# Alim_Ticketing_Slave.net
KiCad netlist of a schematic drawn in Altium Designer
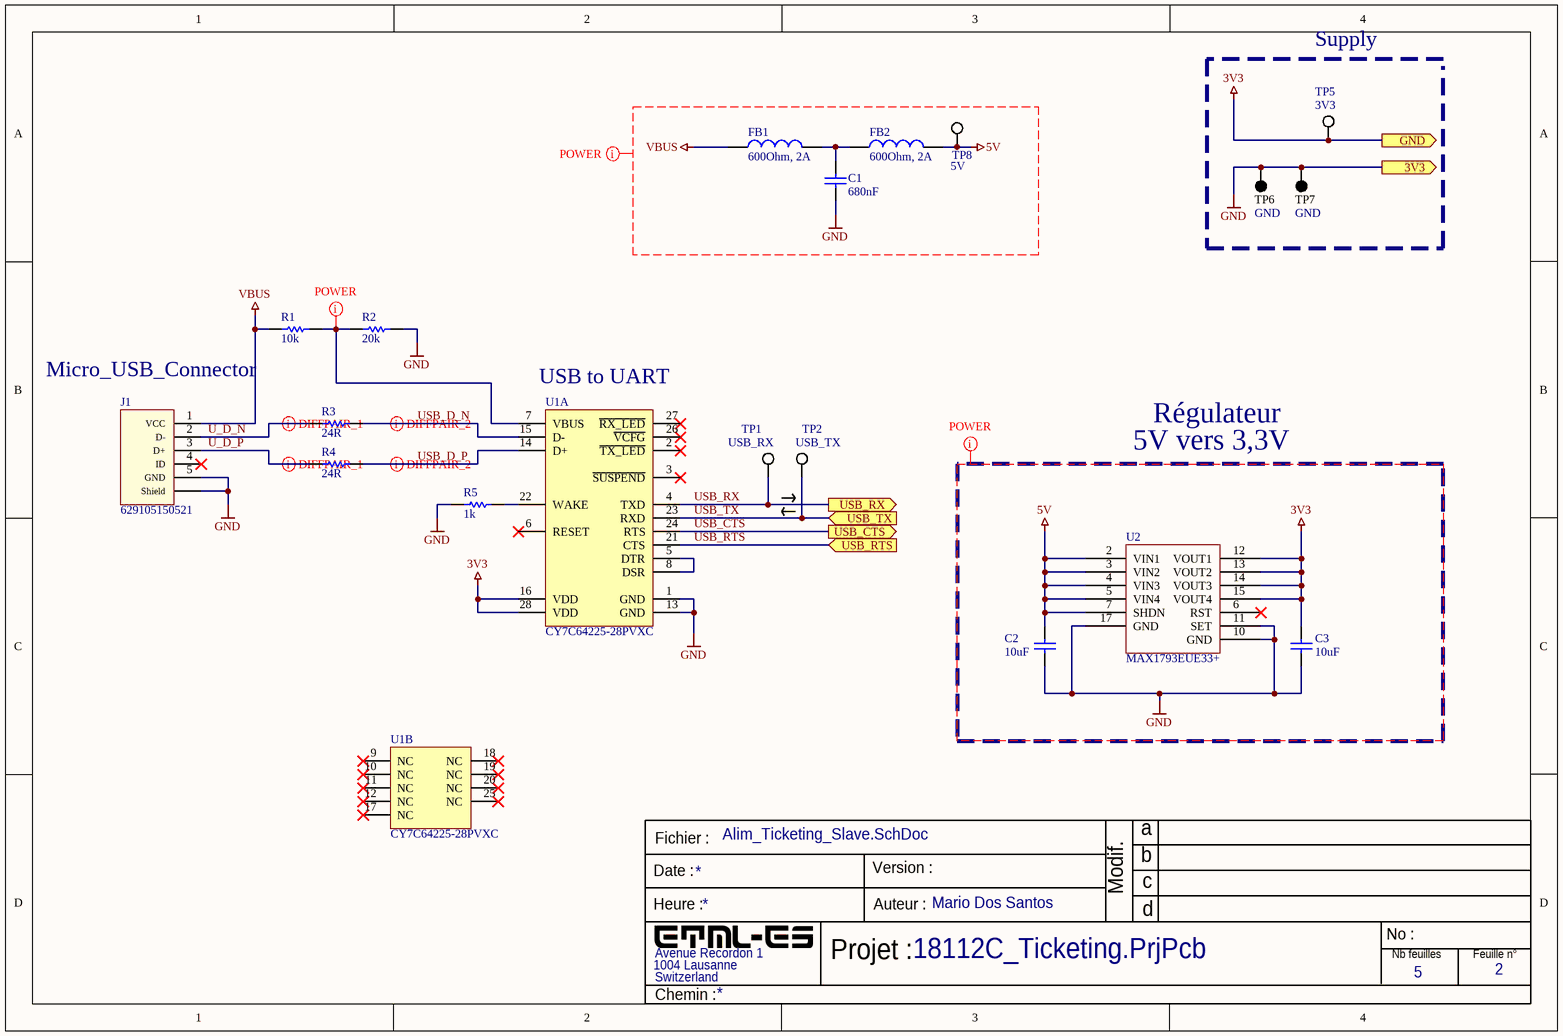
[diagram p0: Alim_Ticketing_Slave.SchDoc]

(export (version "E")
  (design (tool "Eeschema 10.0.6"))
  (components
    (comp (ref "C1")
      (value "680nF")
      (footprint "6-0805_N")
      (description "WCAP-CSGP General Purpose Ceramic Capacitors, size 0805, 100nF, +/-10%, 50VDC")
      (libsource (lib "VPA_v2b") (part "885012207098"))
    )
    (comp (ref "C2")
      (value "10uF")
      (footprint "6-0805_N")
      (description "Capacitor")
      (fields (field (name "PUBLISHER") "Altium Limited"))
      (libsource (lib "Miscellaneous Devices") (part "Cap"))
    )
    (comp (ref "C3")
      (value "10uF")
      (footprint "6-0805_N")
      (description "Capacitor")
      (fields (field (name "PUBLISHER") "Altium Limited"))
      (libsource (lib "Miscellaneous Devices") (part "Cap"))
    )
    (comp (ref "FB1")
      (value "600Ohm, 2A")
      (footprint "WE-CBF_0805_High Current")
      (description "WE-CBF SMT EMI Suppression Ferrite Bead, size 0805, 600Ohm, 2A")
      (fields (field (name "PART NUMBER") "742792040") (field (name "PUBLISHER") "Wurth Elektronik"))
      (libsource (lib "VPA_v2b") (part "742792040"))
    )
    (comp (ref "FB2")
      (value "600Ohm, 2A")
      (footprint "WE-CBF_0805_High Current")
      (description "WE-CBF SMT EMI Suppression Ferrite Bead, size 0805, 600Ohm, 2A")
      (fields (field (name "PART NUMBER") "742792040") (field (name "PUBLISHER") "Wurth Elektronik"))
      (libsource (lib "VPA_v2b") (part "742792040"))
    )
    (comp (ref "J1")
      (value "629105150521")
      (footprint "629105150521")
      (description "Micro USB 2.0 SMT Type B Horizontal 5 Contacts High Current WR-COM")
      (fields (field (name "PART NUMBER") "732-5960-1-ND") (field (name "PUBLISHER") "Wurth Elektronik"))
      (libsource (lib "PCB_Ticketing_Slave") (part "629105150521"))
    )
    (comp (ref "R1")
      (value "10k")
      (footprint "RESC0805(2012)_L")
      (description "100K 0.125W 5% 0805 (2012 Metric)  SMD")
      (fields (field (name "TOLERANCE") "5 %") (field (name "POWER") "0.125 W"))
      (libsource (lib "Altium Content Vault") (part "CMP-1013-00122-1"))
    )
    (comp (ref "R2")
      (value "20k")
      (footprint "RESC0805(2012)_L")
      (description "100K 0.125W 5% 0805 (2012 Metric)  SMD")
      (fields (field (name "TOLERANCE") "5 %") (field (name "POWER") "0.125 W"))
      (libsource (lib "Altium Content Vault") (part "CMP-1013-00122-1"))
    )
    (comp (ref "R3")
      (value "24R")
      (footprint "RESC0805(2012)_L")
      (description "100K 0.125W 5% 0805 (2012 Metric)  SMD")
      (fields (field (name "TOLERANCE") "5 %") (field (name "POWER") "0.125 W"))
      (libsource (lib "Altium Content Vault") (part "CMP-1013-00122-1"))
    )
    (comp (ref "R4")
      (value "24R")
      (footprint "RESC0805(2012)_L")
      (description "100K 0.125W 5% 0805 (2012 Metric)  SMD")
      (fields (field (name "TOLERANCE") "5 %") (field (name "POWER") "0.125 W"))
      (libsource (lib "Altium Content Vault") (part "CMP-1013-00122-1"))
    )
    (comp (ref "R5")
      (value "1k")
      (footprint "RESC0805(2012)_L")
      (description "100K 0.125W 5% 0805 (2012 Metric)  SMD")
      (fields (field (name "TOLERANCE") "5 %") (field (name "POWER") "0.125 W"))
      (libsource (lib "Altium Content Vault") (part "CMP-1013-00122-1"))
    )
    (comp (ref "TP1")
      (value "~")
      (footprint "KSTN-5019_V")
      (description "Test Point, 1 Position SMD, RoHS, Tape and Reel")
      (libsource (lib "Altium Content Vault") (part "TESTPOINT_WHITE"))
    )
    (comp (ref "TP2")
      (value "~")
      (footprint "KSTN-5019_V")
      (description "Test Point, 1 Position SMD, RoHS, Tape and Reel")
      (libsource (lib "Altium Content Vault") (part "TESTPOINT_WHITE"))
    )
    (comp (ref "TP5")
      (value "~")
      (footprint "KSTN-5019_V")
      (description "Test Point, 1 Position SMD, RoHS, Tape and Reel")
      (libsource (lib "Altium Content Vault") (part "TESTPOINT_WHITE"))
    )
    (comp (ref "TP6")
      (value "~")
      (footprint "KSTN-5011_V")
      (description "Test Point, Black, Through Hole, RoHS, Bulk,5011")
      (fields (field (name "MANUFACTURER") "Keystone"))
      (libsource (lib "Altium Content Vault") (part "TESTPOINT_BLACK"))
    )
    (comp (ref "TP7")
      (value "~")
      (footprint "KSTN-5011_V")
      (description "Test Point, Black, Through Hole, RoHS, Bulk,5011")
      (fields (field (name "MANUFACTURER") "Keystone"))
      (libsource (lib "Altium Content Vault") (part "TESTPOINT_BLACK"))
    )
    (comp (ref "TP8")
      (value "~")
      (footprint "KSTN-5019_V")
      (description "Test Point, 1 Position SMD, RoHS, Tape and Reel")
      (libsource (lib "Altium Content Vault") (part "TESTPOINT_WHITE"))
    )
    (comp (ref "U1")
      (value "CY7C64225-28PVXC")
      (footprint "CYP-PVX28_N")
      (description "USB-to-UART Bridge Controller, 3 to 5.25 V, 0 to 70 degC, 28-Pin SSOP (PVX28), Tube")
      (fields (field (name "MANUFACTURER") "Cypress") (field (name "PART NUMBER") "428-3158-ND"))
      (libsource (lib "PCB_Ticketing_Slave") (part "CMP-0967-00143-1"))
    )
    (comp (ref "U2")
      (value "MAX1793EUE33+")
      (footprint "TSOP65P640X110_HS-17N")
      (libsource (lib "2018A_CarteIoEscapeRoom_CAD") (part "MAX1793"))
    )
  )
  (nets
    (net (code "1") (name "/USB_CTS") (class "Default")
      (node (ref "U1") (pin "24") (pinfunction "RTS_24") (pintype "passive"))
    )
    (net (code "2") (name "/USB_D_N") (class "Default")
      (node (ref "R3") (pin "2") (pinfunction "2_2") (pintype "passive"))
      (node (ref "U1") (pin "15") (pinfunction "D-_15") (pintype "passive"))
    )
    (net (code "3") (name "/USB_D_P") (class "Default")
      (node (ref "R4") (pin "2") (pinfunction "2_2") (pintype "passive"))
      (node (ref "U1") (pin "14") (pinfunction "D+_14") (pintype "passive"))
    )
    (net (code "4") (name "/USB_RTS") (class "Default")
      (node (ref "U1") (pin "21") (pinfunction "CTS_21") (pintype "passive"))
    )
    (net (code "5") (name "/USB_RX") (class "Default")
      (node (ref "TP1") (pin "1") (pinfunction "1_1") (pintype "passive"))
      (node (ref "U1") (pin "4") (pinfunction "TXD_4") (pintype "passive"))
    )
    (net (code "6") (name "/USB_TX") (class "Default")
      (node (ref "TP2") (pin "1") (pinfunction "1_1") (pintype "passive"))
      (node (ref "U1") (pin "23") (pinfunction "RXD_23") (pintype "passive"))
    )
    (net (code "7") (name "/U_D_N") (class "Default")
      (node (ref "J1") (pin "2") (pinfunction "D-_2") (pintype "passive"))
      (node (ref "R3") (pin "1") (pinfunction "1_1") (pintype "passive"))
    )
    (net (code "8") (name "/U_D_P") (class "Default")
      (node (ref "J1") (pin "3") (pinfunction "D+_3") (pintype "passive"))
      (node (ref "R4") (pin "1") (pinfunction "1_1") (pintype "passive"))
    )
    (net (code "9") (name "3V3") (class "Default")
      (node (ref "C1") (pin "2") (pinfunction "2_2") (pintype "passive"))
      (node (ref "C2") (pin "2") (pinfunction "2_2") (pintype "passive"))
      (node (ref "C3") (pin "1") (pinfunction "1_1") (pintype "passive"))
      (node (ref "C3") (pin "2") (pinfunction "2_2") (pintype "passive"))
      (node (ref "J1") (pin "5") (pinfunction "GND_5") (pintype "passive"))
      (node (ref "J1") (pin "Shell") (pinfunction "Shield_Shell") (pintype "passive"))
      (node (ref "R2") (pin "2") (pinfunction "2_2") (pintype "passive"))
      (node (ref "R5") (pin "2") (pinfunction "2_2") (pintype "passive"))
      (node (ref "TP5") (pin "1") (pinfunction "1_1") (pintype "passive"))
      (node (ref "TP6") (pin "1") (pinfunction "1_1") (pintype "passive"))
      (node (ref "TP7") (pin "1") (pinfunction "1_1") (pintype "passive"))
      (node (ref "U1") (pin "1") (pinfunction "GND_1") (pintype "passive"))
      (node (ref "U1") (pin "13") (pinfunction "GND_13") (pintype "passive"))
      (node (ref "U1") (pin "16") (pinfunction "VDD_16") (pintype "passive"))
      (node (ref "U1") (pin "28") (pinfunction "VDD_28") (pintype "passive"))
      (node (ref "U2") (pin "10") (pinfunction "GND_10") (pintype "power_in"))
      (node (ref "U2") (pin "11") (pinfunction "SET_11") (pintype "passive"))
      (node (ref "U2") (pin "12") (pinfunction "VOUT1_12") (pintype "passive"))
      (node (ref "U2") (pin "13") (pinfunction "VOUT2_13") (pintype "passive"))
      (node (ref "U2") (pin "14") (pinfunction "VOUT3_14") (pintype "passive"))
      (node (ref "U2") (pin "15") (pinfunction "VOUT4_15") (pintype "passive"))
      (node (ref "U2") (pin "17") (pinfunction "GND_17") (pintype "power_in"))
    )
    (net (code "10") (name "5V") (class "Default")
      (node (ref "C2") (pin "1") (pinfunction "1_1") (pintype "passive"))
      (node (ref "FB2") (pin "2") (pinfunction "2_2") (pintype "passive"))
      (node (ref "TP8") (pin "1") (pinfunction "1_1") (pintype "passive"))
      (node (ref "U2") (pin "2") (pinfunction "VIN1_2") (pintype "passive"))
      (node (ref "U2") (pin "3") (pinfunction "VIN2_3") (pintype "passive"))
      (node (ref "U2") (pin "4") (pinfunction "VIN3_4") (pintype "passive"))
      (node (ref "U2") (pin "5") (pinfunction "VIN4_5") (pintype "passive"))
      (node (ref "U2") (pin "7") (pinfunction "SHDN_7") (pintype "passive"))
    )
    (net (code "11") (name "Net-(C1-Pad1)") (class "Default")
      (node (ref "C1") (pin "1") (pinfunction "1_1") (pintype "passive"))
      (node (ref "FB1") (pin "2") (pinfunction "2_2") (pintype "passive"))
      (node (ref "FB2") (pin "1") (pinfunction "1_1") (pintype "passive"))
    )
    (net (code "12") (name "Net-(U1A-DSR)") (class "Default")
      (node (ref "U1") (pin "5") (pinfunction "DTR_5") (pintype "passive"))
      (node (ref "U1") (pin "8") (pinfunction "DSR_8") (pintype "passive"))
    )
    (net (code "13") (name "Net-(U1A-VBUS)") (class "Default")
      (node (ref "R1") (pin "2") (pinfunction "2_2") (pintype "passive"))
      (node (ref "R2") (pin "1") (pinfunction "1_1") (pintype "passive"))
      (node (ref "U1") (pin "7") (pinfunction "VBUS_7") (pintype "passive"))
    )
    (net (code "14") (name "Net-(U1A-WAKE)") (class "Default")
      (node (ref "R5") (pin "1") (pinfunction "1_1") (pintype "passive"))
      (node (ref "U1") (pin "22") (pinfunction "WAKE_22") (pintype "passive"))
    )
    (net (code "15") (name "VBUS") (class "Default")
      (node (ref "FB1") (pin "1") (pinfunction "1_1") (pintype "passive"))
      (node (ref "J1") (pin "1") (pinfunction "VCC_1") (pintype "passive"))
      (node (ref "R1") (pin "1") (pinfunction "1_1") (pintype "passive"))
    )
    (net (code "16") (name "unconnected-(J1-ID-Pad4)") (class "Default")
      (node (ref "J1") (pin "4") (pinfunction "ID_4") (pintype "passive+no_connect"))
    )
    (net (code "17") (name "unconnected-(U1A-RESET-Pad6)") (class "Default")
      (node (ref "U1") (pin "6") (pinfunction "RESET_6") (pintype "passive+no_connect"))
    )
    (net (code "18") (name "unconnected-(U1A-~{RX_LED}-Pad27)") (class "Default")
      (node (ref "U1") (pin "27") (pinfunction "~{RX_LED}_27") (pintype "passive+no_connect"))
    )
    (net (code "19") (name "unconnected-(U1A-~{SUSPEND}-Pad3)") (class "Default")
      (node (ref "U1") (pin "3") (pinfunction "~{SUSPEND}_3") (pintype "passive+no_connect"))
    )
    (net (code "20") (name "unconnected-(U1A-~{TX_LED}-Pad2)") (class "Default")
      (node (ref "U1") (pin "2") (pinfunction "~{TX_LED}_2") (pintype "passive+no_connect"))
    )
    (net (code "21") (name "unconnected-(U1A-~{VCFG}-Pad26)") (class "Default")
      (node (ref "U1") (pin "26") (pinfunction "~{VCFG}_26") (pintype "passive+no_connect"))
    )
    (net (code "22") (name "unconnected-(U1B-NC-Pad9)") (class "Default")
      (node (ref "U1") (pin "9") (pinfunction "NC_9") (pintype "passive+no_connect"))
    )
    (net (code "23") (name "unconnected-(U1B-NC-Pad10)") (class "Default")
      (node (ref "U1") (pin "10") (pinfunction "NC_10") (pintype "passive+no_connect"))
    )
    (net (code "24") (name "unconnected-(U1B-NC-Pad11)") (class "Default")
      (node (ref "U1") (pin "11") (pinfunction "NC_11") (pintype "passive+no_connect"))
    )
    (net (code "25") (name "unconnected-(U1B-NC-Pad12)") (class "Default")
      (node (ref "U1") (pin "12") (pinfunction "NC_12") (pintype "passive+no_connect"))
    )
    (net (code "26") (name "unconnected-(U1B-NC-Pad17)") (class "Default")
      (node (ref "U1") (pin "17") (pinfunction "NC_17") (pintype "passive+no_connect"))
    )
    (net (code "27") (name "unconnected-(U1B-NC-Pad18)") (class "Default")
      (node (ref "U1") (pin "18") (pinfunction "NC_18") (pintype "passive+no_connect"))
    )
    (net (code "28") (name "unconnected-(U1B-NC-Pad19)") (class "Default")
      (node (ref "U1") (pin "19") (pinfunction "NC_19") (pintype "passive+no_connect"))
    )
    (net (code "29") (name "unconnected-(U1B-NC-Pad20)") (class "Default")
      (node (ref "U1") (pin "20") (pinfunction "NC_20") (pintype "passive+no_connect"))
    )
    (net (code "30") (name "unconnected-(U1B-NC-Pad25)") (class "Default")
      (node (ref "U1") (pin "25") (pinfunction "NC_25") (pintype "passive+no_connect"))
    )
    (net (code "31") (name "unconnected-(U2-RST-Pad6)") (class "Default")
      (node (ref "U2") (pin "6") (pinfunction "RST_6") (pintype "passive+no_connect"))
    )
  )
)
